# Power.net
KiCad netlist of a schematic drawn in Altium Designer
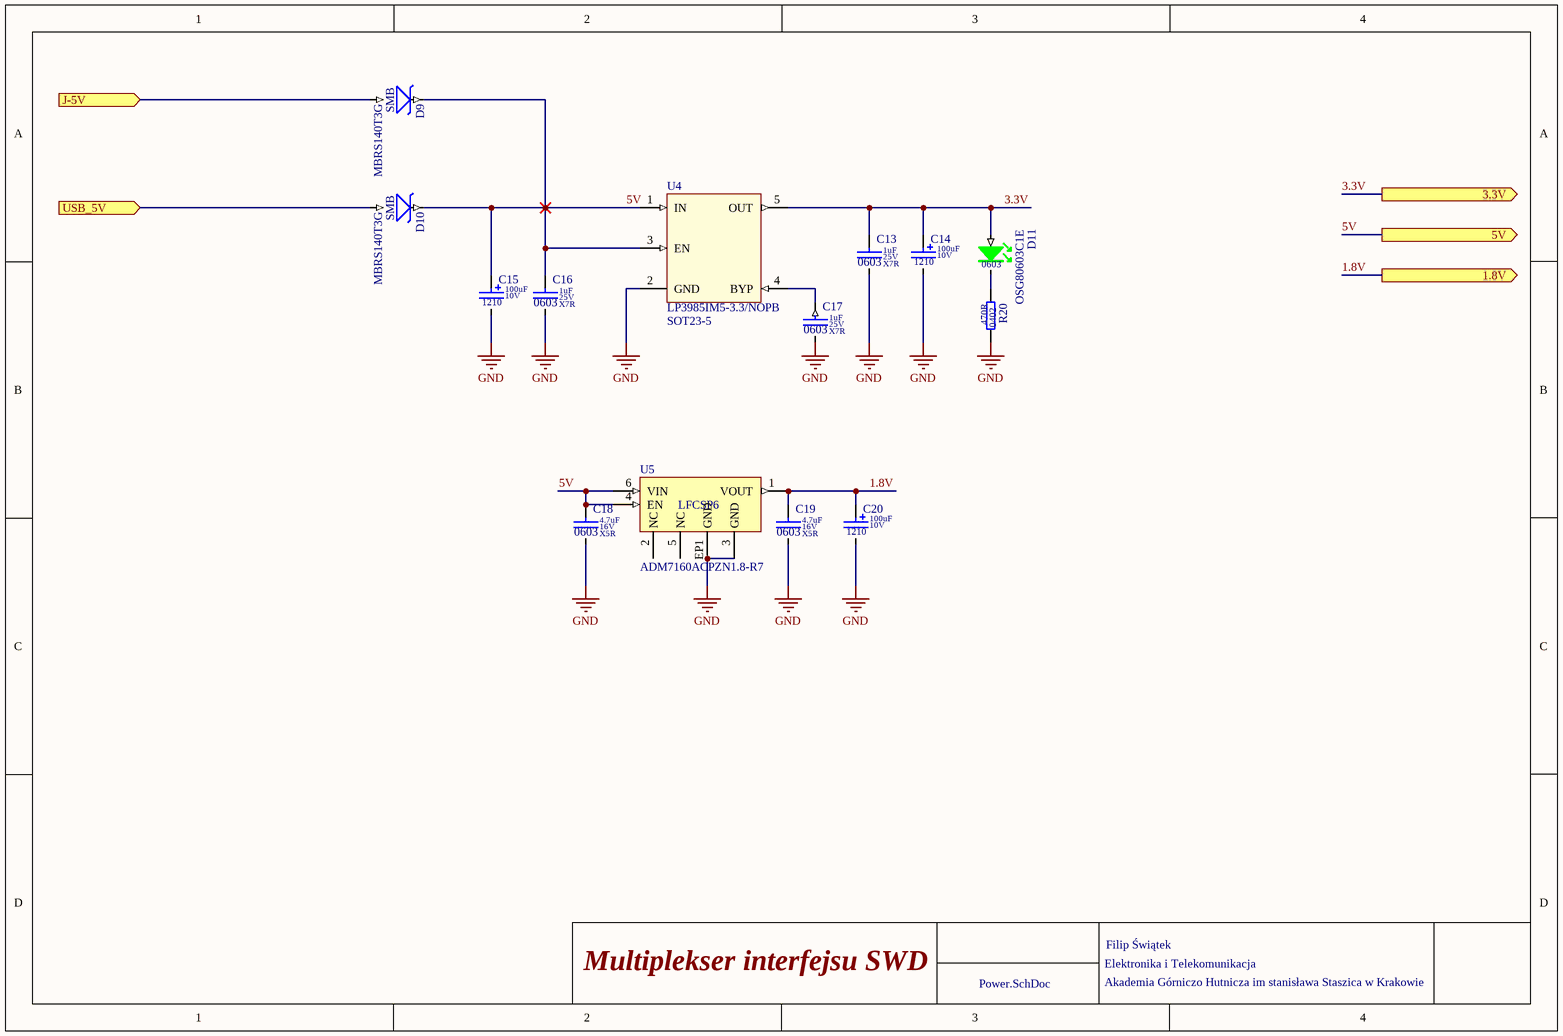
[diagram p0: Power.SchDoc]

(export (version "E")
  (design (tool "Eeschema 10.0.6"))
  (components
    (comp (ref "C13")
      (value "1uF")
      (footprint "C_0603_1608")
      (description "Capacitor")
      (fields
        (field (name "DIELECTRIC") "X7R")
        (field (name "VOLTAGE") "25V")
        (field (name "SCH_FOOTPRINT") "0603")
        (field (name "PART NUMBER") "C_1uF_25V_X7R_0603_10")
        (field (name "MANUFACTURER") "Samsung")
      )
      (libsource (lib "Library") (part "C"))
    )
    (comp (ref "C14")
      (value "100uF")
      (footprint "CT_1210_3225")
      (description "Capacitor")
      (fields
        (field (name "SCH_FOOTPRINT") "1210")
        (field (name "VOLTAGE") "10V")
        (field (name "PART NUMBER") "CT_100uF_10V_TA2O5_1210_20")
        (field (name "MANUFACTURER") "AVX")
      )
      (libsource (lib "Library") (part "CT"))
    )
    (comp (ref "C15")
      (value "100uF")
      (footprint "CT_1210_3225")
      (description "Capacitor")
      (fields
        (field (name "SCH_FOOTPRINT") "1210")
        (field (name "VOLTAGE") "10V")
        (field (name "PART NUMBER") "CT_100uF_10V_TA2O5_1210_20")
        (field (name "MANUFACTURER") "AVX")
      )
      (libsource (lib "Library") (part "CT"))
    )
    (comp (ref "C16")
      (value "1uF")
      (footprint "C_0603_1608")
      (description "Capacitor")
      (fields
        (field (name "DIELECTRIC") "X7R")
        (field (name "VOLTAGE") "25V")
        (field (name "SCH_FOOTPRINT") "0603")
        (field (name "PART NUMBER") "C_1uF_25V_X7R_0603_10")
        (field (name "MANUFACTURER") "Samsung")
      )
      (libsource (lib "Library") (part "C"))
    )
    (comp (ref "C17")
      (value "1uF")
      (footprint "C_0603_1608")
      (description "Capacitor")
      (fields
        (field (name "DIELECTRIC") "X7R")
        (field (name "VOLTAGE") "25V")
        (field (name "SCH_FOOTPRINT") "0603")
        (field (name "PART NUMBER") "C_1uF_25V_X7R_0603_10")
        (field (name "MANUFACTURER") "Samsung")
      )
      (libsource (lib "") (part "C_1"))
    )
    (comp (ref "C18")
      (value "4.7uF")
      (footprint "C_0603_1608")
      (description "Capacitor")
      (fields
        (field (name "DIELECTRIC") "X5R")
        (field (name "VOLTAGE") "16V")
        (field (name "SCH_FOOTPRINT") "0603")
        (field (name "PART NUMBER") "C_4.7uF_16V_X5R_0603_10")
        (field (name "MANUFACTURER") "Murata")
      )
      (libsource (lib "Library") (part "C"))
    )
    (comp (ref "C19")
      (value "4.7uF")
      (footprint "C_0603_1608")
      (description "Capacitor")
      (fields
        (field (name "DIELECTRIC") "X5R")
        (field (name "VOLTAGE") "16V")
        (field (name "SCH_FOOTPRINT") "0603")
        (field (name "PART NUMBER") "C_4.7uF_16V_X5R_0603_10")
        (field (name "MANUFACTURER") "Murata")
      )
      (libsource (lib "Library") (part "C"))
    )
    (comp (ref "C20")
      (value "100uF")
      (footprint "CT_1210_3225")
      (description "Capacitor")
      (fields
        (field (name "SCH_FOOTPRINT") "1210")
        (field (name "VOLTAGE") "10V")
        (field (name "PART NUMBER") "CT_100uF_10V_TA2O5_1210_20")
        (field (name "MANUFACTURER") "AVX")
      )
      (libsource (lib "Library") (part "CT"))
    )
    (comp (ref "D9")
      (value "MBRS140T3G")
      (footprint "SMB_DO-214AA")
      (fields
        (field (name "SCH_FOOTPRINT") "SMB")
        (field (name "PART NUMBER") "DS_MBRS140T3G_1A_40V_SMB")
        (field (name "VOLTAGE") "40V")
        (field (name "MANUFACTURER") "ON Semiconductor")
      )
      (libsource (lib "Library") (part "DS"))
    )
    (comp (ref "D10")
      (value "MBRS140T3G")
      (footprint "SMB_DO-214AA")
      (fields
        (field (name "SCH_FOOTPRINT") "SMB")
        (field (name "PART NUMBER") "DS_MBRS140T3G_1A_40V_SMB")
        (field (name "VOLTAGE") "40V")
        (field (name "MANUFACTURER") "ON Semiconductor")
      )
      (libsource (lib "Library") (part "DS"))
    )
    (comp (ref "D11")
      (value "OSG80603C1E")
      (footprint "OL_0603_1608")
      (description "LED GREEN")
      (fields
        (field (name "SCH_FOOTPRINT") "0603")
        (field (name "PART NUMBER") "OL_G_0603_OSG80603C1E")
        (field (name "MANUFACTURER") "Optosupply")
      )
      (libsource (lib "Library") (part "OL_G"))
    )
    (comp (ref "R20")
      (value "470R")
      (footprint "R_0402_1005")
      (fields
        (field (name "SCH_FOOTPRINT") "0402")
        (field (name "PART NUMBER") "R_470R_0402_1")
        (field (name "VOLTAGE") "50V")
        (field (name "POWER") "63mW")
      )
      (libsource (lib "Library") (part "R"))
    )
    (comp (ref "U4")
      (value "LP3985IM5-3.3/NOPB")
      (footprint "SOT23-5_SC74A_SOT753_M")
      (fields
        (field (name "SCH_FOOTPRINT") "SOT23-5")
        (field (name "PART NUMBER") "VL_LP3985IM5-3.3")
        (field (name "VOLTAGE") "3V3")
        (field (name "MANUFACTURER") "Texas Instruments")
      )
      (libsource (lib "Library") (part "VL_LP3985IM5"))
    )
    (comp (ref "U5")
      (value "ADM7160ACPZN1.8-R7")
      (footprint "LFCSP-6-3")
      (fields
        (field (name "SCH_FOOTPRINT") "LFCSP6")
        (field (name "PART NUMBER") "VL_ADM7160ACPZN1.8-R7")
        (field (name "VOLTAGE") "1V8")
        (field (name "MANUFACTURER") "Analog Devices")
      )
      (libsource (lib "Library") (part "VL_ADM7160ACPZN"))
    )
  )
  (nets
    (net (code "1") (name "/1.8V") (class "Default")
      (node (ref "C19") (pin "1") (pinfunction "1_1") (pintype "passive"))
      (node (ref "C20") (pin "1") (pinfunction "1_1") (pintype "passive"))
      (node (ref "U5") (pin "1") (pinfunction "VOUT_1") (pintype "output"))
    )
    (net (code "2") (name "/3.3V") (class "Default")
      (node (ref "C13") (pin "1") (pinfunction "1_1") (pintype "passive"))
      (node (ref "C14") (pin "1") (pinfunction "1_1") (pintype "passive"))
      (node (ref "D11") (pin "2") (pinfunction "A_2") (pintype "input"))
      (node (ref "U4") (pin "5") (pinfunction "OUT_5") (pintype "output"))
    )
    (net (code "3") (name "/5V") (class "Default")
      (node (ref "C15") (pin "1") (pinfunction "1_1") (pintype "passive"))
      (node (ref "C16") (pin "1") (pinfunction "1_1") (pintype "passive"))
      (node (ref "C18") (pin "1") (pinfunction "1_1") (pintype "passive"))
      (node (ref "D10") (pin "1") (pintype "output"))
      (node (ref "D9") (pin "1") (pintype "output"))
      (node (ref "U4") (pin "1") (pinfunction "IN_1") (pintype "input"))
      (node (ref "U4") (pin "3") (pinfunction "EN_3") (pintype "input"))
      (node (ref "U5") (pin "4") (pinfunction "EN_4") (pintype "input"))
      (node (ref "U5") (pin "6") (pinfunction "VIN_6") (pintype "input"))
    )
    (net (code "4") (name "/J-5V") (class "Default") (node (ref "D9") (pin "2") (pintype "input")))
    (net (code "5") (name "/USB_5V") (class "Default") (node (ref "D10") (pin "2") (pintype "input")))
    (net (code "6") (name "GND") (class "Default")
      (node (ref "C13") (pin "2") (pinfunction "2_2") (pintype "passive"))
      (node (ref "C14") (pin "2") (pinfunction "2_2") (pintype "passive"))
      (node (ref "C15") (pin "2") (pinfunction "2_2") (pintype "passive"))
      (node (ref "C16") (pin "2") (pinfunction "2_2") (pintype "passive"))
      (node (ref "C17") (pin "2") (pinfunction "2_2") (pintype "input"))
      (node (ref "C18") (pin "2") (pinfunction "2_2") (pintype "passive"))
      (node (ref "C19") (pin "2") (pinfunction "2_2") (pintype "passive"))
      (node (ref "C20") (pin "2") (pinfunction "2_2") (pintype "passive"))
      (node (ref "R20") (pin "2") (pinfunction "2_2") (pintype "passive"))
      (node (ref "U4") (pin "2") (pinfunction "GND_2") (pintype "power_in"))
      (node (ref "U5") (pin "3") (pinfunction "GND_3") (pintype "power_in"))
      (node (ref "U5") (pin "EP1") (pinfunction "GND_EP1") (pintype "power_in"))
    )
    (net (code "7") (name "Net-(D11-K)") (class "Default")
      (node (ref "D11") (pin "1") (pinfunction "K_1") (pintype "output"))
      (node (ref "R20") (pin "1") (pinfunction "1_1") (pintype "passive"))
    )
    (net (code "8") (name "Net-(U4-BYP)") (class "Default")
      (node (ref "C17") (pin "1") (pinfunction "1_1") (pintype "output"))
      (node (ref "U4") (pin "4") (pinfunction "BYP_4") (pintype "input"))
    )
    (net (code "9") (name "unconnected-(U5-NC-Pad2)") (class "Default")
      (node (ref "U5") (pin "2") (pinfunction "NC_2") (pintype "passive"))
    )
    (net (code "10") (name "unconnected-(U5-NC-Pad5)") (class "Default")
      (node (ref "U5") (pin "5") (pinfunction "NC_5") (pintype "passive"))
    )
  )
)
